# EmbiggenedKeyboard.net
KiCad netlist of a schematic drawn in EAGLE
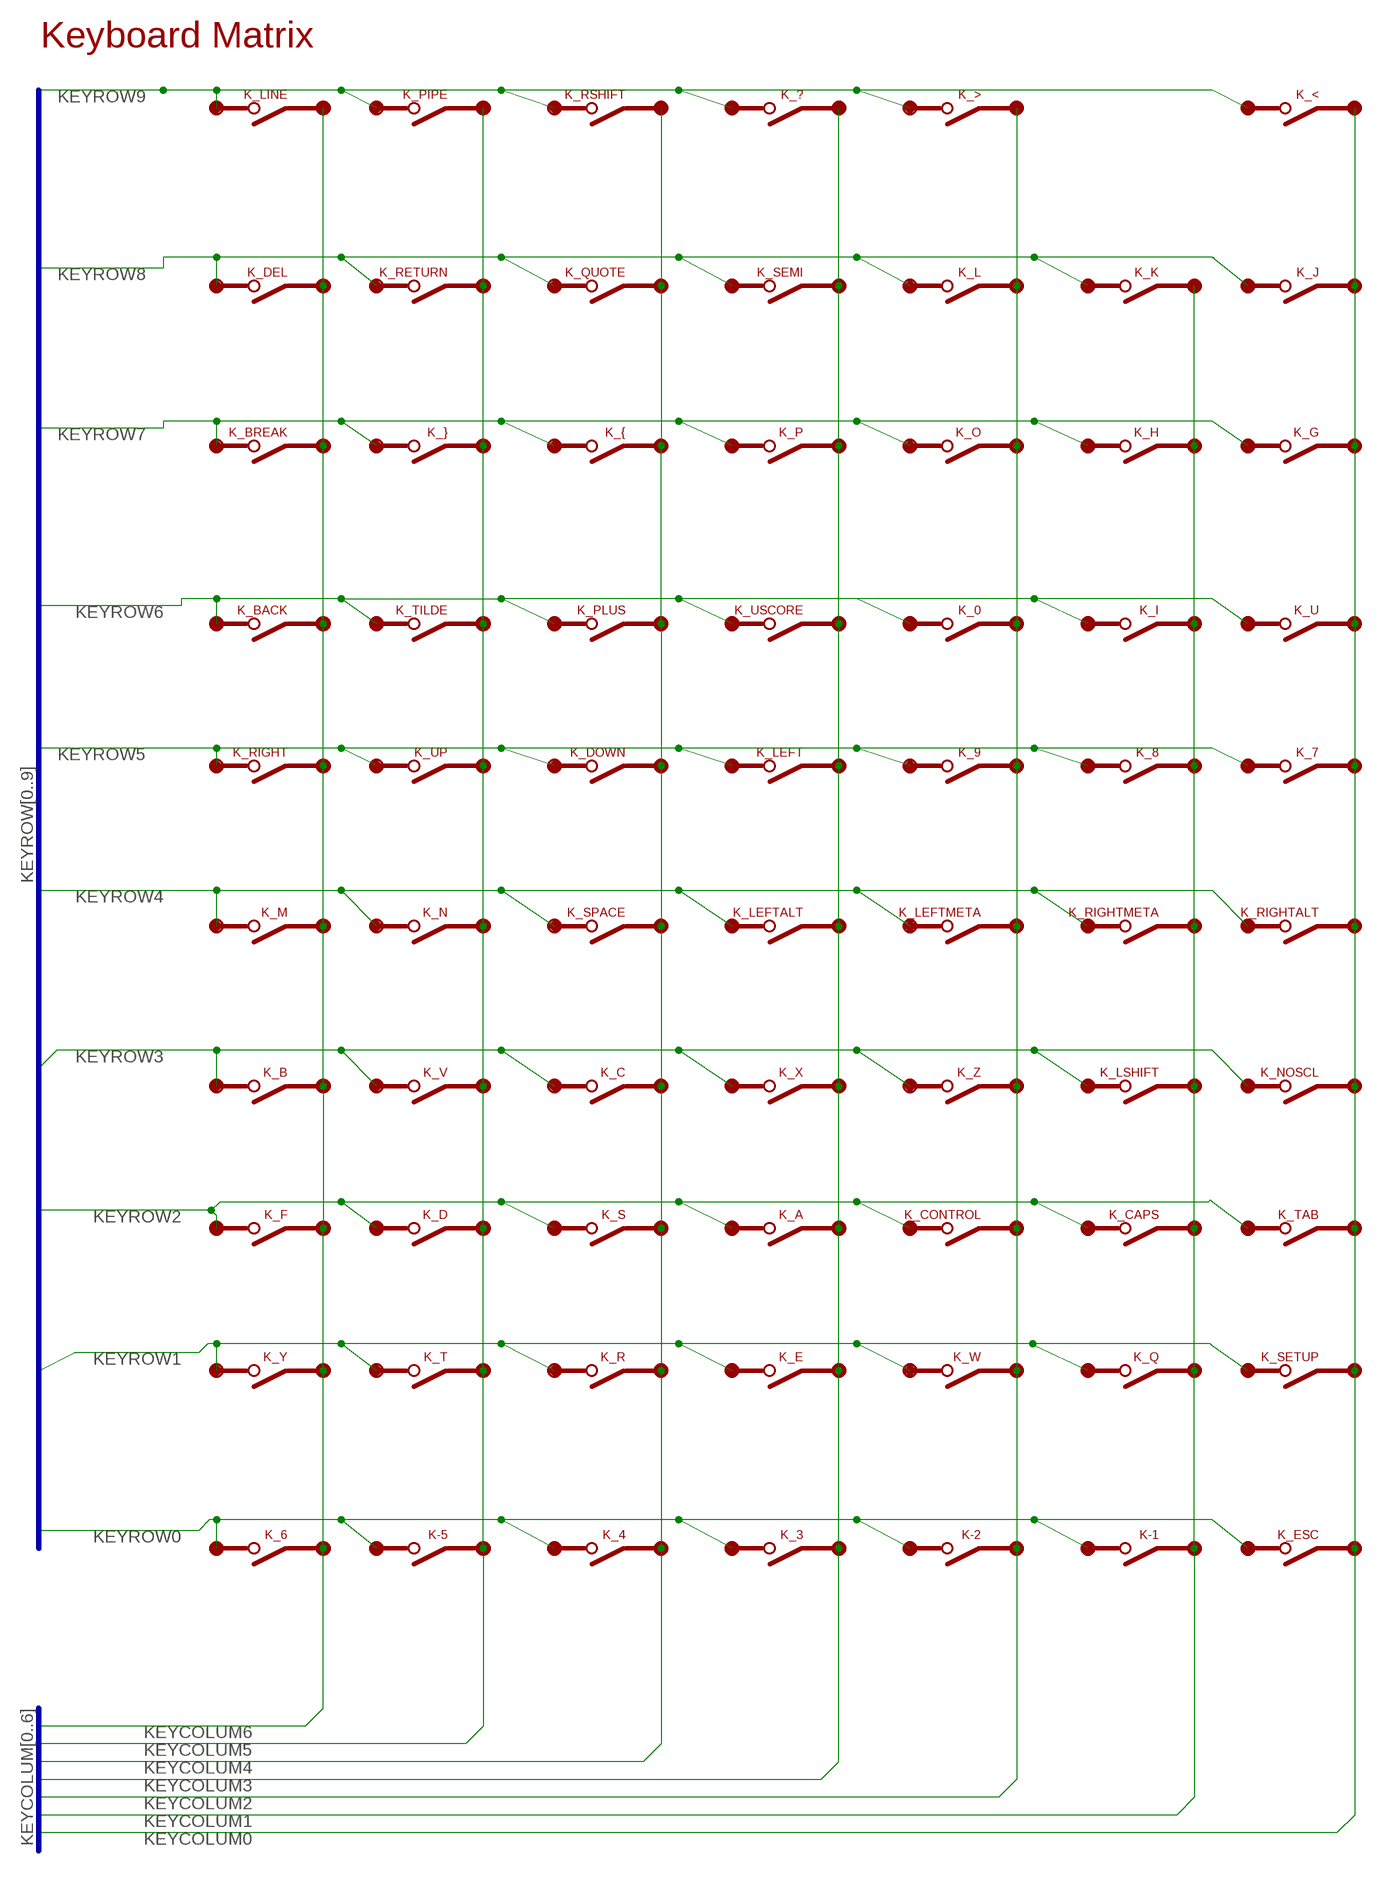
[diagram p0: schematic, sheet 1, part 1 of 2]
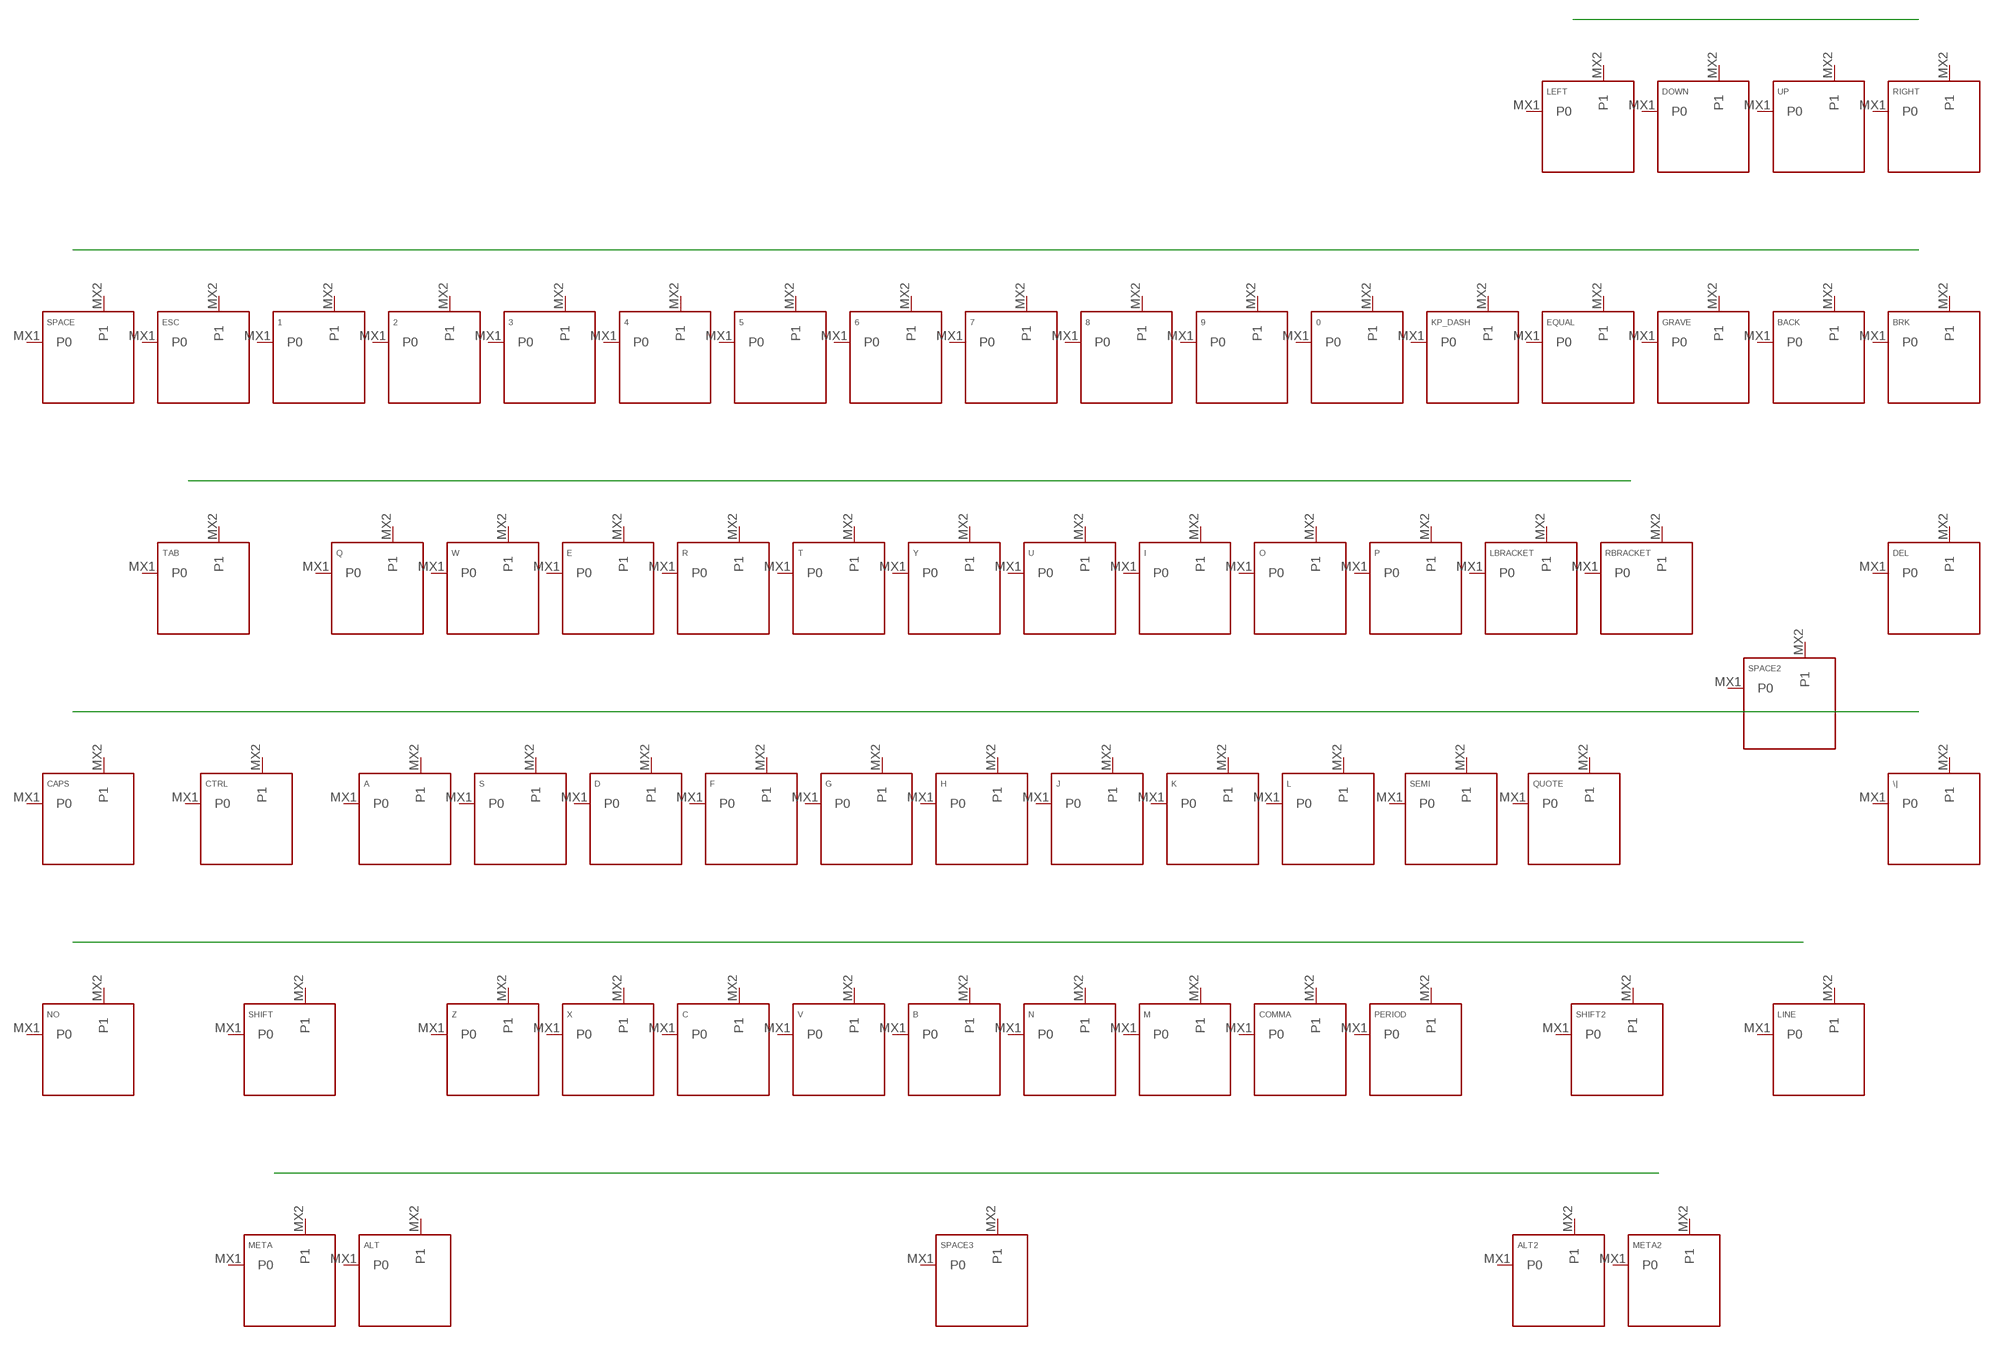
[diagram p1: schematic, sheet 1, part 2 of 2]

(export (version "E")
  (design (tool "Eeschema 10.0.6"))
  (components
    (comp (ref "0")
      (value "KEYSWITCH-PLAIN-MX-1U")
      (footprint "eagle-import:MX-1U")
      (libsource (lib "eagle-import") (part "KEYSWITCH-PLAIN-MX-1U"))
    )
    (comp (ref "1")
      (value "KEYSWITCH-PLAIN-MX-1U")
      (footprint "eagle-import:MX-1U")
      (libsource (lib "eagle-import") (part "KEYSWITCH-PLAIN-MX-1U"))
    )
    (comp (ref "2")
      (value "KEYSWITCH-PLAIN-MX-1U")
      (footprint "eagle-import:MX-1U")
      (libsource (lib "eagle-import") (part "KEYSWITCH-PLAIN-MX-1U"))
    )
    (comp (ref "3")
      (value "KEYSWITCH-PLAIN-MX-1U")
      (footprint "eagle-import:MX-1U")
      (libsource (lib "eagle-import") (part "KEYSWITCH-PLAIN-MX-1U"))
    )
    (comp (ref "4")
      (value "KEYSWITCH-PLAIN-MX-1U")
      (footprint "eagle-import:MX-1U")
      (libsource (lib "eagle-import") (part "KEYSWITCH-PLAIN-MX-1U"))
    )
    (comp (ref "5")
      (value "KEYSWITCH-PLAIN-MX-1U")
      (footprint "eagle-import:MX-1U")
      (libsource (lib "eagle-import") (part "KEYSWITCH-PLAIN-MX-1U"))
    )
    (comp (ref "6")
      (value "KEYSWITCH-PLAIN-MX-1U")
      (footprint "eagle-import:MX-1U")
      (libsource (lib "eagle-import") (part "KEYSWITCH-PLAIN-MX-1U"))
    )
    (comp (ref "7")
      (value "KEYSWITCH-PLAIN-MX-1U")
      (footprint "eagle-import:MX-1U")
      (libsource (lib "eagle-import") (part "KEYSWITCH-PLAIN-MX-1U"))
    )
    (comp (ref "8")
      (value "KEYSWITCH-PLAIN-MX-1U")
      (footprint "eagle-import:MX-1U")
      (libsource (lib "eagle-import") (part "KEYSWITCH-PLAIN-MX-1U"))
    )
    (comp (ref "9")
      (value "KEYSWITCH-PLAIN-MX-1U")
      (footprint "eagle-import:MX-1U")
      (libsource (lib "eagle-import") (part "KEYSWITCH-PLAIN-MX-1U"))
    )
    (comp (ref "A")
      (value "KEYSWITCH-PLAIN-MX-1U")
      (footprint "eagle-import:MX-1U")
      (libsource (lib "eagle-import") (part "KEYSWITCH-PLAIN-MX-1U"))
    )
    (comp (ref "ALT")
      (value "KEYSWITCH-PLAIN-MX-1U")
      (footprint "eagle-import:MX-1U")
      (libsource (lib "eagle-import") (part "KEYSWITCH-PLAIN-MX-1U"))
    )
    (comp (ref "ALT2")
      (value "KEYSWITCH-PLAIN-MX-1U")
      (footprint "eagle-import:MX-1U")
      (libsource (lib "eagle-import") (part "KEYSWITCH-PLAIN-MX-1U"))
    )
    (comp (ref "B")
      (value "KEYSWITCH-PLAIN-MX-1U")
      (footprint "eagle-import:MX-1U")
      (libsource (lib "eagle-import") (part "KEYSWITCH-PLAIN-MX-1U"))
    )
    (comp (ref "BACK")
      (value "KEYSWITCH-PLAIN-MX-1U")
      (footprint "eagle-import:MX-1U")
      (libsource (lib "eagle-import") (part "KEYSWITCH-PLAIN-MX-1U"))
    )
    (comp (ref "BRK")
      (value "KEYSWITCH-PLAIN-MX-1U")
      (footprint "eagle-import:MX-1U")
      (libsource (lib "eagle-import") (part "KEYSWITCH-PLAIN-MX-1U"))
    )
    (comp (ref "C")
      (value "KEYSWITCH-PLAIN-MX-1U")
      (footprint "eagle-import:MX-1U")
      (libsource (lib "eagle-import") (part "KEYSWITCH-PLAIN-MX-1U"))
    )
    (comp (ref "CAPS")
      (value "KEYSWITCH-PLAIN-MX-1U")
      (footprint "eagle-import:MX-1U")
      (libsource (lib "eagle-import") (part "KEYSWITCH-PLAIN-MX-1U"))
    )
    (comp (ref "COMMA")
      (value "KEYSWITCH-PLAIN-MX-1U")
      (footprint "eagle-import:MX-1U")
      (libsource (lib "eagle-import") (part "KEYSWITCH-PLAIN-MX-1U"))
    )
    (comp (ref "CTRL")
      (value "KEYSWITCH-PLAIN-MX-1U")
      (footprint "eagle-import:MX-1U")
      (libsource (lib "eagle-import") (part "KEYSWITCH-PLAIN-MX-1U"))
    )
    (comp (ref "D")
      (value "KEYSWITCH-PLAIN-MX-1U")
      (footprint "eagle-import:MX-1U")
      (libsource (lib "eagle-import") (part "KEYSWITCH-PLAIN-MX-1U"))
    )
    (comp (ref "DEL")
      (value "KEYSWITCH-PLAIN-MX-1U")
      (footprint "eagle-import:MX-1U")
      (libsource (lib "eagle-import") (part "KEYSWITCH-PLAIN-MX-1U"))
    )
    (comp (ref "DOWN")
      (value "KEYSWITCH-PLAIN-MX-1U")
      (footprint "eagle-import:MX-1U")
      (libsource (lib "eagle-import") (part "KEYSWITCH-PLAIN-MX-1U"))
    )
    (comp (ref "E")
      (value "KEYSWITCH-PLAIN-MX-1U")
      (footprint "eagle-import:MX-1U")
      (libsource (lib "eagle-import") (part "KEYSWITCH-PLAIN-MX-1U"))
    )
    (comp (ref "EQUAL")
      (value "KEYSWITCH-PLAIN-MX-1U")
      (footprint "eagle-import:MX-1U")
      (libsource (lib "eagle-import") (part "KEYSWITCH-PLAIN-MX-1U"))
    )
    (comp (ref "ESC")
      (value "KEYSWITCH-PLAIN-MX-1U")
      (footprint "eagle-import:MX-1U")
      (libsource (lib "eagle-import") (part "KEYSWITCH-PLAIN-MX-1U"))
    )
    (comp (ref "F")
      (value "KEYSWITCH-PLAIN-MX-1U")
      (footprint "eagle-import:MX-1U")
      (libsource (lib "eagle-import") (part "KEYSWITCH-PLAIN-MX-1U"))
    )
    (comp (ref "G")
      (value "KEYSWITCH-PLAIN-MX-1U")
      (footprint "eagle-import:MX-1U")
      (libsource (lib "eagle-import") (part "KEYSWITCH-PLAIN-MX-1U"))
    )
    (comp (ref "GRAVE")
      (value "KEYSWITCH-PLAIN-MX-1U")
      (footprint "eagle-import:MX-1U")
      (libsource (lib "eagle-import") (part "KEYSWITCH-PLAIN-MX-1U"))
    )
    (comp (ref "H")
      (value "KEYSWITCH-PLAIN-MX-1U")
      (footprint "eagle-import:MX-1U")
      (libsource (lib "eagle-import") (part "KEYSWITCH-PLAIN-MX-1U"))
    )
    (comp (ref "I")
      (value "KEYSWITCH-PLAIN-MX-1U")
      (footprint "eagle-import:MX-1U")
      (libsource (lib "eagle-import") (part "KEYSWITCH-PLAIN-MX-1U"))
    )
    (comp (ref "J")
      (value "KEYSWITCH-PLAIN-MX-1U")
      (footprint "eagle-import:MX-1U")
      (libsource (lib "eagle-import") (part "KEYSWITCH-PLAIN-MX-1U"))
    )
    (comp (ref "K")
      (value "KEYSWITCH-PLAIN-MX-1U")
      (footprint "eagle-import:MX-1U")
      (libsource (lib "eagle-import") (part "KEYSWITCH-PLAIN-MX-1U"))
    )
    (comp (ref "K-1")
      (value "1U_PAD")
      (footprint "eagle-import:SILICONE_SWITCH")
      (libsource (lib "eagle-import") (part "1U_PAD"))
    )
    (comp (ref "K-2")
      (value "1U_PAD")
      (footprint "eagle-import:SILICONE_SWITCH")
      (libsource (lib "eagle-import") (part "1U_PAD"))
    )
    (comp (ref "K-5")
      (value "1U_PAD")
      (footprint "eagle-import:SILICONE_SWITCH")
      (libsource (lib "eagle-import") (part "1U_PAD"))
    )
    (comp (ref "KP_DASH")
      (value "KEYSWITCH-PLAIN-MX-1U")
      (footprint "eagle-import:MX-1U")
      (libsource (lib "eagle-import") (part "KEYSWITCH-PLAIN-MX-1U"))
    )
    (comp (ref "K_0")
      (value "1U_PAD")
      (footprint "eagle-import:SILICONE_SWITCH")
      (libsource (lib "eagle-import") (part "1U_PAD"))
    )
    (comp (ref "K_3")
      (value "1U_PAD")
      (footprint "eagle-import:SILICONE_SWITCH")
      (libsource (lib "eagle-import") (part "1U_PAD"))
    )
    (comp (ref "K_4")
      (value "1U_PAD")
      (footprint "eagle-import:SILICONE_SWITCH")
      (libsource (lib "eagle-import") (part "1U_PAD"))
    )
    (comp (ref "K_6")
      (value "1U_PAD")
      (footprint "eagle-import:SILICONE_SWITCH")
      (libsource (lib "eagle-import") (part "1U_PAD"))
    )
    (comp (ref "K_7")
      (value "1U_PAD")
      (footprint "eagle-import:SILICONE_SWITCH")
      (libsource (lib "eagle-import") (part "1U_PAD"))
    )
    (comp (ref "K_8")
      (value "1U_PAD")
      (footprint "eagle-import:SILICONE_SWITCH")
      (libsource (lib "eagle-import") (part "1U_PAD"))
    )
    (comp (ref "K_9")
      (value "1U_PAD")
      (footprint "eagle-import:SILICONE_SWITCH")
      (libsource (lib "eagle-import") (part "1U_PAD"))
    )
    (comp (ref "K_<")
      (value "1U_PAD")
      (footprint "eagle-import:SILICONE_SWITCH")
      (libsource (lib "eagle-import") (part "1U_PAD"))
    )
    (comp (ref "K_>")
      (value "1U_PAD")
      (footprint "eagle-import:SILICONE_SWITCH")
      (libsource (lib "eagle-import") (part "1U_PAD"))
    )
    (comp (ref "K_?")
      (value "1U_PAD")
      (footprint "eagle-import:SILICONE_SWITCH")
      (libsource (lib "eagle-import") (part "1U_PAD"))
    )
    (comp (ref "K_A")
      (value "1U_PAD")
      (footprint "eagle-import:SILICONE_SWITCH")
      (libsource (lib "eagle-import") (part "1U_PAD"))
    )
    (comp (ref "K_B")
      (value "1U_PAD")
      (footprint "eagle-import:SILICONE_SWITCH")
      (libsource (lib "eagle-import") (part "1U_PAD"))
    )
    (comp (ref "K_BACK")
      (value "1U_PAD")
      (footprint "eagle-import:SILICONE_SWITCH")
      (libsource (lib "eagle-import") (part "1U_PAD"))
    )
    (comp (ref "K_BREAK")
      (value "1U_PAD")
      (footprint "eagle-import:SILICONE_SWITCH")
      (libsource (lib "eagle-import") (part "1U_PAD"))
    )
    (comp (ref "K_C")
      (value "1U_PAD")
      (footprint "eagle-import:SILICONE_SWITCH")
      (libsource (lib "eagle-import") (part "1U_PAD"))
    )
    (comp (ref "K_CAPS")
      (value "1U_PAD")
      (footprint "eagle-import:SILICONE_SWITCH")
      (libsource (lib "eagle-import") (part "1U_PAD"))
    )
    (comp (ref "K_CONTROL")
      (value "2U_PAD")
      (footprint "eagle-import:SILICONE_SWITCH_2U")
      (libsource (lib "eagle-import") (part "2U_PAD"))
    )
    (comp (ref "K_D")
      (value "1U_PAD")
      (footprint "eagle-import:SILICONE_SWITCH")
      (libsource (lib "eagle-import") (part "1U_PAD"))
    )
    (comp (ref "K_DEL")
      (value "1U_PAD")
      (footprint "eagle-import:SILICONE_SWITCH")
      (libsource (lib "eagle-import") (part "1U_PAD"))
    )
    (comp (ref "K_DOWN")
      (value "1U_PAD")
      (footprint "eagle-import:SILICONE_SWITCH")
      (libsource (lib "eagle-import") (part "1U_PAD"))
    )
    (comp (ref "K_E")
      (value "1U_PAD")
      (footprint "eagle-import:SILICONE_SWITCH")
      (libsource (lib "eagle-import") (part "1U_PAD"))
    )
    (comp (ref "K_ESC")
      (value "1U_PAD")
      (footprint "eagle-import:SILICONE_SWITCH")
      (libsource (lib "eagle-import") (part "1U_PAD"))
    )
    (comp (ref "K_F")
      (value "1U_PAD")
      (footprint "eagle-import:SILICONE_SWITCH")
      (libsource (lib "eagle-import") (part "1U_PAD"))
    )
    (comp (ref "K_G")
      (value "1U_PAD")
      (footprint "eagle-import:SILICONE_SWITCH")
      (libsource (lib "eagle-import") (part "1U_PAD"))
    )
    (comp (ref "K_H")
      (value "1U_PAD")
      (footprint "eagle-import:SILICONE_SWITCH")
      (libsource (lib "eagle-import") (part "1U_PAD"))
    )
    (comp (ref "K_I")
      (value "1U_PAD")
      (footprint "eagle-import:SILICONE_SWITCH")
      (libsource (lib "eagle-import") (part "1U_PAD"))
    )
    (comp (ref "K_J")
      (value "1U_PAD")
      (footprint "eagle-import:SILICONE_SWITCH")
      (libsource (lib "eagle-import") (part "1U_PAD"))
    )
    (comp (ref "K_K")
      (value "1U_PAD")
      (footprint "eagle-import:SILICONE_SWITCH")
      (libsource (lib "eagle-import") (part "1U_PAD"))
    )
    (comp (ref "K_L")
      (value "1U_PAD")
      (footprint "eagle-import:SILICONE_SWITCH")
      (libsource (lib "eagle-import") (part "1U_PAD"))
    )
    (comp (ref "K_LEFT")
      (value "1U_PAD")
      (footprint "eagle-import:SILICONE_SWITCH")
      (libsource (lib "eagle-import") (part "1U_PAD"))
    )
    (comp (ref "K_LEFTALT")
      (value "1U_PAD")
      (footprint "eagle-import:SILICONE_SWITCH")
      (libsource (lib "eagle-import") (part "1U_PAD"))
    )
    (comp (ref "K_LEFTMETA")
      (value "1U_PAD")
      (footprint "eagle-import:SILICONE_SWITCH")
      (libsource (lib "eagle-import") (part "1U_PAD"))
    )
    (comp (ref "K_LINE")
      (value "1U_PAD")
      (footprint "eagle-import:SILICONE_SWITCH")
      (libsource (lib "eagle-import") (part "1U_PAD"))
    )
    (comp (ref "K_LSHIFT")
      (value "2U_PAD")
      (footprint "eagle-import:SILICONE_SWITCH_2U")
      (libsource (lib "eagle-import") (part "2U_PAD"))
    )
    (comp (ref "K_M")
      (value "1U_PAD")
      (footprint "eagle-import:SILICONE_SWITCH")
      (libsource (lib "eagle-import") (part "1U_PAD"))
    )
    (comp (ref "K_N")
      (value "1U_PAD")
      (footprint "eagle-import:SILICONE_SWITCH")
      (libsource (lib "eagle-import") (part "1U_PAD"))
    )
    (comp (ref "K_NOSCL")
      (value "1U_PAD")
      (footprint "eagle-import:SILICONE_SWITCH")
      (libsource (lib "eagle-import") (part "1U_PAD"))
    )
    (comp (ref "K_O")
      (value "1U_PAD")
      (footprint "eagle-import:SILICONE_SWITCH")
      (libsource (lib "eagle-import") (part "1U_PAD"))
    )
    (comp (ref "K_P")
      (value "1U_PAD")
      (footprint "eagle-import:SILICONE_SWITCH")
      (libsource (lib "eagle-import") (part "1U_PAD"))
    )
    (comp (ref "K_PIPE")
      (value "1U_PAD")
      (footprint "eagle-import:SILICONE_SWITCH")
      (libsource (lib "eagle-import") (part "1U_PAD"))
    )
    (comp (ref "K_PLUS")
      (value "1U_PAD")
      (footprint "eagle-import:SILICONE_SWITCH")
      (libsource (lib "eagle-import") (part "1U_PAD"))
    )
    (comp (ref "K_Q")
      (value "1U_PAD")
      (footprint "eagle-import:SILICONE_SWITCH")
      (libsource (lib "eagle-import") (part "1U_PAD"))
    )
    (comp (ref "K_QUOTE")
      (value "1U_PAD")
      (footprint "eagle-import:SILICONE_SWITCH")
      (libsource (lib "eagle-import") (part "1U_PAD"))
    )
    (comp (ref "K_R")
      (value "1U_PAD")
      (footprint "eagle-import:SILICONE_SWITCH")
      (libsource (lib "eagle-import") (part "1U_PAD"))
    )
    (comp (ref "K_RETURN")
      (value "RETURN_PAD")
      (footprint "eagle-import:SILICONE_RETURN")
      (libsource (lib "eagle-import") (part "RETURN_PAD"))
    )
    (comp (ref "K_RIGHT")
      (value "1U_PAD")
      (footprint "eagle-import:SILICONE_SWITCH")
      (libsource (lib "eagle-import") (part "1U_PAD"))
    )
    (comp (ref "K_RIGHTALT")
      (value "1U_PAD")
      (footprint "eagle-import:SILICONE_SWITCH")
      (libsource (lib "eagle-import") (part "1U_PAD"))
    )
    (comp (ref "K_RIGHTMETA")
      (value "1U_PAD")
      (footprint "eagle-import:SILICONE_SWITCH")
      (libsource (lib "eagle-import") (part "1U_PAD"))
    )
    (comp (ref "K_RSHIFT")
      (value "2U_PAD")
      (footprint "eagle-import:SILICONE_SWITCH_2U")
      (libsource (lib "eagle-import") (part "2U_PAD"))
    )
    (comp (ref "K_S")
      (value "1U_PAD")
      (footprint "eagle-import:SILICONE_SWITCH")
      (libsource (lib "eagle-import") (part "1U_PAD"))
    )
    (comp (ref "K_SEMI")
      (value "1U_PAD")
      (footprint "eagle-import:SILICONE_SWITCH")
      (libsource (lib "eagle-import") (part "1U_PAD"))
    )
    (comp (ref "K_SETUP")
      (value "2U_PAD")
      (footprint "eagle-import:SILICONE_SWITCH_2U")
      (libsource (lib "eagle-import") (part "2U_PAD"))
    )
    (comp (ref "K_SPACE")
      (value "SPACE_PAD")
      (footprint "eagle-import:SILICONE_SPACE")
      (libsource (lib "eagle-import") (part "SPACE_PAD"))
    )
    (comp (ref "K_T")
      (value "1U_PAD")
      (footprint "eagle-import:SILICONE_SWITCH")
      (libsource (lib "eagle-import") (part "1U_PAD"))
    )
    (comp (ref "K_TAB")
      (value "1U_PAD")
      (footprint "eagle-import:SILICONE_SWITCH")
      (libsource (lib "eagle-import") (part "1U_PAD"))
    )
    (comp (ref "K_TILDE")
      (value "1U_PAD")
      (footprint "eagle-import:SILICONE_SWITCH")
      (libsource (lib "eagle-import") (part "1U_PAD"))
    )
    (comp (ref "K_U")
      (value "1U_PAD")
      (footprint "eagle-import:SILICONE_SWITCH")
      (libsource (lib "eagle-import") (part "1U_PAD"))
    )
    (comp (ref "K_UP")
      (value "1U_PAD")
      (footprint "eagle-import:SILICONE_SWITCH")
      (libsource (lib "eagle-import") (part "1U_PAD"))
    )
    (comp (ref "K_USCORE")
      (value "1U_PAD")
      (footprint "eagle-import:SILICONE_SWITCH")
      (libsource (lib "eagle-import") (part "1U_PAD"))
    )
    (comp (ref "K_V")
      (value "1U_PAD")
      (footprint "eagle-import:SILICONE_SWITCH")
      (libsource (lib "eagle-import") (part "1U_PAD"))
    )
    (comp (ref "K_W")
      (value "1U_PAD")
      (footprint "eagle-import:SILICONE_SWITCH")
      (libsource (lib "eagle-import") (part "1U_PAD"))
    )
    (comp (ref "K_X")
      (value "1U_PAD")
      (footprint "eagle-import:SILICONE_SWITCH")
      (libsource (lib "eagle-import") (part "1U_PAD"))
    )
    (comp (ref "K_Y")
      (value "1U_PAD")
      (footprint "eagle-import:SILICONE_SWITCH")
      (libsource (lib "eagle-import") (part "1U_PAD"))
    )
    (comp (ref "K_Z")
      (value "1U_PAD")
      (footprint "eagle-import:SILICONE_SWITCH")
      (libsource (lib "eagle-import") (part "1U_PAD"))
    )
    (comp (ref "K_{")
      (value "1U_PAD")
      (footprint "eagle-import:SILICONE_SWITCH")
      (libsource (lib "eagle-import") (part "1U_PAD"))
    )
    (comp (ref "K_}")
      (value "1U_PAD")
      (footprint "eagle-import:SILICONE_SWITCH")
      (libsource (lib "eagle-import") (part "1U_PAD"))
    )
    (comp (ref "L")
      (value "KEYSWITCH-PLAIN-MX-1U")
      (footprint "eagle-import:MX-1U")
      (libsource (lib "eagle-import") (part "KEYSWITCH-PLAIN-MX-1U"))
    )
    (comp (ref "LBRACKET")
      (value "KEYSWITCH-PLAIN-MX-1U")
      (footprint "eagle-import:MX-1U")
      (libsource (lib "eagle-import") (part "KEYSWITCH-PLAIN-MX-1U"))
    )
    (comp (ref "LEFT")
      (value "KEYSWITCH-PLAIN-MX-1U")
      (footprint "eagle-import:MX-1U")
      (libsource (lib "eagle-import") (part "KEYSWITCH-PLAIN-MX-1U"))
    )
    (comp (ref "LINE")
      (value "KEYSWITCH-PLAIN-MX-1U")
      (footprint "eagle-import:MX-1U")
      (libsource (lib "eagle-import") (part "KEYSWITCH-PLAIN-MX-1U"))
    )
    (comp (ref "M")
      (value "KEYSWITCH-PLAIN-MX-1U")
      (footprint "eagle-import:MX-1U")
      (libsource (lib "eagle-import") (part "KEYSWITCH-PLAIN-MX-1U"))
    )
    (comp (ref "META")
      (value "KEYSWITCH-PLAIN-MX-1U")
      (footprint "eagle-import:MX-1U")
      (libsource (lib "eagle-import") (part "KEYSWITCH-PLAIN-MX-1U"))
    )
    (comp (ref "META2")
      (value "KEYSWITCH-PLAIN-MX-1U")
      (footprint "eagle-import:MX-1U")
      (libsource (lib "eagle-import") (part "KEYSWITCH-PLAIN-MX-1U"))
    )
    (comp (ref "N")
      (value "KEYSWITCH-PLAIN-MX-1U")
      (footprint "eagle-import:MX-1U")
      (libsource (lib "eagle-import") (part "KEYSWITCH-PLAIN-MX-1U"))
    )
    (comp (ref "NO")
      (value "KEYSWITCH-PLAIN-MX-1U")
      (footprint "eagle-import:MX-1U")
      (libsource (lib "eagle-import") (part "KEYSWITCH-PLAIN-MX-1U"))
    )
    (comp (ref "O")
      (value "KEYSWITCH-PLAIN-MX-1U")
      (footprint "eagle-import:MX-1U")
      (libsource (lib "eagle-import") (part "KEYSWITCH-PLAIN-MX-1U"))
    )
    (comp (ref "P")
      (value "KEYSWITCH-PLAIN-MX-1U")
      (footprint "eagle-import:MX-1U")
      (libsource (lib "eagle-import") (part "KEYSWITCH-PLAIN-MX-1U"))
    )
    (comp (ref "PERIOD")
      (value "KEYSWITCH-PLAIN-MX-1U")
      (footprint "eagle-import:MX-1U")
      (libsource (lib "eagle-import") (part "KEYSWITCH-PLAIN-MX-1U"))
    )
    (comp (ref "Q")
      (value "KEYSWITCH-PLAIN-MX-1U")
      (footprint "eagle-import:MX-1U")
      (libsource (lib "eagle-import") (part "KEYSWITCH-PLAIN-MX-1U"))
    )
    (comp (ref "QUOTE")
      (value "KEYSWITCH-PLAIN-MX-1U")
      (footprint "eagle-import:MX-1U")
      (libsource (lib "eagle-import") (part "KEYSWITCH-PLAIN-MX-1U"))
    )
    (comp (ref "R")
      (value "KEYSWITCH-PLAIN-MX-1U")
      (footprint "eagle-import:MX-1U")
      (libsource (lib "eagle-import") (part "KEYSWITCH-PLAIN-MX-1U"))
    )
    (comp (ref "RBRACKET")
      (value "KEYSWITCH-PLAIN-MX-1U")
      (footprint "eagle-import:MX-1U")
      (libsource (lib "eagle-import") (part "KEYSWITCH-PLAIN-MX-1U"))
    )
    (comp (ref "RIGHT")
      (value "KEYSWITCH-PLAIN-MX-1U")
      (footprint "eagle-import:MX-1U")
      (libsource (lib "eagle-import") (part "KEYSWITCH-PLAIN-MX-1U"))
    )
    (comp (ref "S")
      (value "KEYSWITCH-PLAIN-MX-1U")
      (footprint "eagle-import:MX-1U")
      (libsource (lib "eagle-import") (part "KEYSWITCH-PLAIN-MX-1U"))
    )
    (comp (ref "SEMI")
      (value "KEYSWITCH-PLAIN-MX-1U")
      (footprint "eagle-import:MX-1U")
      (libsource (lib "eagle-import") (part "KEYSWITCH-PLAIN-MX-1U"))
    )
    (comp (ref "SHIFT")
      (value "KEYSWITCH-PLAIN-MX-1U")
      (footprint "eagle-import:MX-1U")
      (libsource (lib "eagle-import") (part "KEYSWITCH-PLAIN-MX-1U"))
    )
    (comp (ref "SHIFT2")
      (value "KEYSWITCH-PLAIN-MX-1U")
      (footprint "eagle-import:MX-1U")
      (libsource (lib "eagle-import") (part "KEYSWITCH-PLAIN-MX-1U"))
    )
    (comp (ref "SPACE")
      (value "KEYSWITCH-PLAIN-MX-1U")
      (footprint "eagle-import:MX-1U")
      (libsource (lib "eagle-import") (part "KEYSWITCH-PLAIN-MX-1U"))
    )
    (comp (ref "SPACE2")
      (value "KEYSWITCH-PLAIN-MX-1U")
      (footprint "eagle-import:MX-1U")
      (libsource (lib "eagle-import") (part "KEYSWITCH-PLAIN-MX-1U"))
    )
    (comp (ref "SPACE3")
      (value "KEYSWITCH-PLAIN-MX-1U")
      (footprint "eagle-import:MX-1U")
      (libsource (lib "eagle-import") (part "KEYSWITCH-PLAIN-MX-1U"))
    )
    (comp (ref "T")
      (value "KEYSWITCH-PLAIN-MX-1U")
      (footprint "eagle-import:MX-1U")
      (libsource (lib "eagle-import") (part "KEYSWITCH-PLAIN-MX-1U"))
    )
    (comp (ref "TAB")
      (value "KEYSWITCH-PLAIN-MX-1U")
      (footprint "eagle-import:MX-1U")
      (libsource (lib "eagle-import") (part "KEYSWITCH-PLAIN-MX-1U"))
    )
    (comp (ref "U")
      (value "KEYSWITCH-PLAIN-MX-1U")
      (footprint "eagle-import:MX-1U")
      (libsource (lib "eagle-import") (part "KEYSWITCH-PLAIN-MX-1U"))
    )
    (comp (ref "UP")
      (value "KEYSWITCH-PLAIN-MX-1U")
      (footprint "eagle-import:MX-1U")
      (libsource (lib "eagle-import") (part "KEYSWITCH-PLAIN-MX-1U"))
    )
    (comp (ref "V")
      (value "KEYSWITCH-PLAIN-MX-1U")
      (footprint "eagle-import:MX-1U")
      (libsource (lib "eagle-import") (part "KEYSWITCH-PLAIN-MX-1U"))
    )
    (comp (ref "W")
      (value "KEYSWITCH-PLAIN-MX-1U")
      (footprint "eagle-import:MX-1U")
      (libsource (lib "eagle-import") (part "KEYSWITCH-PLAIN-MX-1U"))
    )
    (comp (ref "X")
      (value "KEYSWITCH-PLAIN-MX-1U")
      (footprint "eagle-import:MX-1U")
      (libsource (lib "eagle-import") (part "KEYSWITCH-PLAIN-MX-1U"))
    )
    (comp (ref "Y")
      (value "KEYSWITCH-PLAIN-MX-1U")
      (footprint "eagle-import:MX-1U")
      (libsource (lib "eagle-import") (part "KEYSWITCH-PLAIN-MX-1U"))
    )
    (comp (ref "Z")
      (value "KEYSWITCH-PLAIN-MX-1U")
      (footprint "eagle-import:MX-1U")
      (libsource (lib "eagle-import") (part "KEYSWITCH-PLAIN-MX-1U"))
    )
    (comp (ref "\\|")
      (value "KEYSWITCH-PLAIN-MX-1U")
      (footprint "eagle-import:MX-1U")
      (libsource (lib "eagle-import") (part "KEYSWITCH-PLAIN-MX-1U"))
    )
  )
  (nets
    (net (code "1") (name "/KEYCOLUM0") (class "Default")
      (node (ref "K_7") (pin "P$2") (pinfunction "P$2_P$2") (pintype "bidirectional"))
      (node (ref "K_<") (pin "P$2") (pinfunction "P$2_P$2") (pintype "bidirectional"))
      (node (ref "K_ESC") (pin "P$2") (pinfunction "P$2_P$2") (pintype "bidirectional"))
      (node (ref "K_G") (pin "P$2") (pinfunction "P$2_P$2") (pintype "bidirectional"))
      (node (ref "K_J") (pin "P$2") (pinfunction "P$2_P$2") (pintype "bidirectional"))
      (node (ref "K_NOSCL") (pin "P$2") (pinfunction "P$2_P$2") (pintype "bidirectional"))
      (node (ref "K_RIGHTALT") (pin "P$2") (pinfunction "P$2_P$2") (pintype "bidirectional"))
      (node (ref "K_SETUP") (pin "P$2") (pinfunction "P$2_P$2") (pintype "bidirectional"))
      (node (ref "K_TAB") (pin "P$2") (pinfunction "P$2_P$2") (pintype "bidirectional"))
      (node (ref "K_U") (pin "P$2") (pinfunction "P$2_P$2") (pintype "bidirectional"))
    )
    (net (code "2") (name "/KEYCOLUM1") (class "Default")
      (node (ref "K-1") (pin "P$2") (pinfunction "P$2_P$2") (pintype "bidirectional"))
      (node (ref "K_8") (pin "P$2") (pinfunction "P$2_P$2") (pintype "bidirectional"))
      (node (ref "K_CAPS") (pin "P$2") (pinfunction "P$2_P$2") (pintype "bidirectional"))
      (node (ref "K_H") (pin "P$2") (pinfunction "P$2_P$2") (pintype "bidirectional"))
      (node (ref "K_I") (pin "P$2") (pinfunction "P$2_P$2") (pintype "bidirectional"))
      (node (ref "K_K") (pin "P$2") (pinfunction "P$2_P$2") (pintype "bidirectional"))
      (node (ref "K_LSHIFT") (pin "P$2") (pinfunction "P$2_P$2") (pintype "bidirectional"))
      (node (ref "K_Q") (pin "P$2") (pinfunction "P$2_P$2") (pintype "bidirectional"))
      (node (ref "K_RIGHTMETA") (pin "P$2") (pinfunction "P$2_P$2") (pintype "bidirectional"))
    )
    (net (code "3") (name "/KEYCOLUM2") (class "Default")
      (node (ref "K-2") (pin "P$2") (pinfunction "P$2_P$2") (pintype "bidirectional"))
      (node (ref "K_0") (pin "P$2") (pinfunction "P$2_P$2") (pintype "bidirectional"))
      (node (ref "K_9") (pin "P$2") (pinfunction "P$2_P$2") (pintype "bidirectional"))
      (node (ref "K_>") (pin "P$2") (pinfunction "P$2_P$2") (pintype "bidirectional"))
      (node (ref "K_CONTROL") (pin "P$2") (pinfunction "P$2_P$2") (pintype "bidirectional"))
      (node (ref "K_L") (pin "P$2") (pinfunction "P$2_P$2") (pintype "bidirectional"))
      (node (ref "K_LEFTMETA") (pin "P$2") (pinfunction "P$2_P$2") (pintype "bidirectional"))
      (node (ref "K_O") (pin "P$2") (pinfunction "P$2_P$2") (pintype "bidirectional"))
      (node (ref "K_W") (pin "P$2") (pinfunction "P$2_P$2") (pintype "bidirectional"))
      (node (ref "K_Z") (pin "P$2") (pinfunction "P$2_P$2") (pintype "bidirectional"))
    )
    (net (code "4") (name "/KEYCOLUM3") (class "Default")
      (node (ref "K_3") (pin "P$2") (pinfunction "P$2_P$2") (pintype "bidirectional"))
      (node (ref "K_?") (pin "P$2") (pinfunction "P$2_P$2") (pintype "bidirectional"))
      (node (ref "K_A") (pin "P$2") (pinfunction "P$2_P$2") (pintype "bidirectional"))
      (node (ref "K_E") (pin "P$2") (pinfunction "P$2_P$2") (pintype "bidirectional"))
      (node (ref "K_LEFT") (pin "P$2") (pinfunction "P$2_P$2") (pintype "bidirectional"))
      (node (ref "K_LEFTALT") (pin "P$2") (pinfunction "P$2_P$2") (pintype "bidirectional"))
      (node (ref "K_P") (pin "P$2") (pinfunction "P$2_P$2") (pintype "bidirectional"))
      (node (ref "K_SEMI") (pin "P$2") (pinfunction "P$2_P$2") (pintype "bidirectional"))
      (node (ref "K_USCORE") (pin "P$2") (pinfunction "P$2_P$2") (pintype "bidirectional"))
      (node (ref "K_X") (pin "P$2") (pinfunction "P$2_P$2") (pintype "bidirectional"))
    )
    (net (code "5") (name "/KEYCOLUM4") (class "Default")
      (node (ref "K_4") (pin "P$2") (pinfunction "P$2_P$2") (pintype "bidirectional"))
      (node (ref "K_C") (pin "P$2") (pinfunction "P$2_P$2") (pintype "bidirectional"))
      (node (ref "K_DOWN") (pin "P$2") (pinfunction "P$2_P$2") (pintype "bidirectional"))
      (node (ref "K_PLUS") (pin "P$2") (pinfunction "P$2_P$2") (pintype "bidirectional"))
      (node (ref "K_QUOTE") (pin "P$2") (pinfunction "P$2_P$2") (pintype "bidirectional"))
      (node (ref "K_R") (pin "P$2") (pinfunction "P$2_P$2") (pintype "bidirectional"))
      (node (ref "K_RSHIFT") (pin "P$2") (pinfunction "P$2_P$2") (pintype "bidirectional"))
      (node (ref "K_S") (pin "P$2") (pinfunction "P$2_P$2") (pintype "bidirectional"))
      (node (ref "K_SPACE") (pin "P$2") (pinfunction "P$2_P$2") (pintype "bidirectional"))
      (node (ref "K_{") (pin "P$2") (pinfunction "P$2_P$2") (pintype "bidirectional"))
    )
    (net (code "6") (name "/KEYCOLUM5") (class "Default")
      (node (ref "K-5") (pin "P$2") (pinfunction "P$2_P$2") (pintype "bidirectional"))
      (node (ref "K_D") (pin "P$2") (pinfunction "P$2_P$2") (pintype "bidirectional"))
      (node (ref "K_N") (pin "P$2") (pinfunction "P$2_P$2") (pintype "bidirectional"))
      (node (ref "K_PIPE") (pin "P$2") (pinfunction "P$2_P$2") (pintype "bidirectional"))
      (node (ref "K_RETURN") (pin "P$2") (pinfunction "P$2_P$2") (pintype "bidirectional"))
      (node (ref "K_T") (pin "P$2") (pinfunction "P$2_P$2") (pintype "bidirectional"))
      (node (ref "K_TILDE") (pin "P$2") (pinfunction "P$2_P$2") (pintype "bidirectional"))
      (node (ref "K_UP") (pin "P$2") (pinfunction "P$2_P$2") (pintype "bidirectional"))
      (node (ref "K_V") (pin "P$2") (pinfunction "P$2_P$2") (pintype "bidirectional"))
      (node (ref "K_}") (pin "P$2") (pinfunction "P$2_P$2") (pintype "bidirectional"))
    )
    (net (code "7") (name "/KEYCOLUM6") (class "Default")
      (node (ref "K_6") (pin "P$2") (pinfunction "P$2_P$2") (pintype "bidirectional"))
      (node (ref "K_B") (pin "P$2") (pinfunction "P$2_P$2") (pintype "bidirectional"))
      (node (ref "K_BACK") (pin "P$2") (pinfunction "P$2_P$2") (pintype "bidirectional"))
      (node (ref "K_BREAK") (pin "P$2") (pinfunction "P$2_P$2") (pintype "bidirectional"))
      (node (ref "K_DEL") (pin "P$2") (pinfunction "P$2_P$2") (pintype "bidirectional"))
      (node (ref "K_F") (pin "P$2") (pinfunction "P$2_P$2") (pintype "bidirectional"))
      (node (ref "K_LINE") (pin "P$2") (pinfunction "P$2_P$2") (pintype "bidirectional"))
      (node (ref "K_M") (pin "P$2") (pinfunction "P$2_P$2") (pintype "bidirectional"))
      (node (ref "K_RIGHT") (pin "P$2") (pinfunction "P$2_P$2") (pintype "bidirectional"))
      (node (ref "K_Y") (pin "P$2") (pinfunction "P$2_P$2") (pintype "bidirectional"))
    )
    (net (code "9") (name "/KEYROW0") (class "Default")
      (node (ref "K-1") (pin "P$1") (pinfunction "P$1_P$1") (pintype "bidirectional"))
      (node (ref "K-2") (pin "P$1") (pinfunction "P$1_P$1") (pintype "bidirectional"))
      (node (ref "K-5") (pin "P$1") (pinfunction "P$1_P$1") (pintype "bidirectional"))
      (node (ref "K_3") (pin "P$1") (pinfunction "P$1_P$1") (pintype "bidirectional"))
      (node (ref "K_4") (pin "P$1") (pinfunction "P$1_P$1") (pintype "bidirectional"))
      (node (ref "K_6") (pin "P$1") (pinfunction "P$1_P$1") (pintype "bidirectional"))
      (node (ref "K_ESC") (pin "P$1") (pinfunction "P$1_P$1") (pintype "bidirectional"))
    )
    (net (code "10") (name "/KEYROW1") (class "Default")
      (node (ref "K_E") (pin "P$1") (pinfunction "P$1_P$1") (pintype "bidirectional"))
      (node (ref "K_Q") (pin "P$1") (pinfunction "P$1_P$1") (pintype "bidirectional"))
      (node (ref "K_R") (pin "P$1") (pinfunction "P$1_P$1") (pintype "bidirectional"))
      (node (ref "K_SETUP") (pin "P$1") (pinfunction "P$1_P$1") (pintype "bidirectional"))
      (node (ref "K_T") (pin "P$1") (pinfunction "P$1_P$1") (pintype "bidirectional"))
      (node (ref "K_W") (pin "P$1") (pinfunction "P$1_P$1") (pintype "bidirectional"))
      (node (ref "K_Y") (pin "P$1") (pinfunction "P$1_P$1") (pintype "bidirectional"))
    )
    (net (code "11") (name "/KEYROW2") (class "Default")
      (node (ref "K_A") (pin "P$1") (pinfunction "P$1_P$1") (pintype "bidirectional"))
      (node (ref "K_CAPS") (pin "P$1") (pinfunction "P$1_P$1") (pintype "bidirectional"))
      (node (ref "K_CONTROL") (pin "P$1") (pinfunction "P$1_P$1") (pintype "bidirectional"))
      (node (ref "K_D") (pin "P$1") (pinfunction "P$1_P$1") (pintype "bidirectional"))
      (node (ref "K_F") (pin "P$1") (pinfunction "P$1_P$1") (pintype "bidirectional"))
      (node (ref "K_S") (pin "P$1") (pinfunction "P$1_P$1") (pintype "bidirectional"))
      (node (ref "K_TAB") (pin "P$1") (pinfunction "P$1_P$1") (pintype "bidirectional"))
    )
    (net (code "12") (name "/KEYROW3") (class "Default")
      (node (ref "K_B") (pin "P$1") (pinfunction "P$1_P$1") (pintype "bidirectional"))
      (node (ref "K_C") (pin "P$1") (pinfunction "P$1_P$1") (pintype "bidirectional"))
      (node (ref "K_LSHIFT") (pin "P$1") (pinfunction "P$1_P$1") (pintype "bidirectional"))
      (node (ref "K_NOSCL") (pin "P$1") (pinfunction "P$1_P$1") (pintype "bidirectional"))
      (node (ref "K_V") (pin "P$1") (pinfunction "P$1_P$1") (pintype "bidirectional"))
      (node (ref "K_X") (pin "P$1") (pinfunction "P$1_P$1") (pintype "bidirectional"))
      (node (ref "K_Z") (pin "P$1") (pinfunction "P$1_P$1") (pintype "bidirectional"))
    )
    (net (code "13") (name "/KEYROW4") (class "Default")
      (node (ref "K_LEFTALT") (pin "P$1") (pinfunction "P$1_P$1") (pintype "bidirectional"))
      (node (ref "K_LEFTMETA") (pin "P$1") (pinfunction "P$1_P$1") (pintype "bidirectional"))
      (node (ref "K_M") (pin "P$1") (pinfunction "P$1_P$1") (pintype "bidirectional"))
      (node (ref "K_N") (pin "P$1") (pinfunction "P$1_P$1") (pintype "bidirectional"))
      (node (ref "K_RIGHTALT") (pin "P$1") (pinfunction "P$1_P$1") (pintype "bidirectional"))
      (node (ref "K_RIGHTMETA") (pin "P$1") (pinfunction "P$1_P$1") (pintype "bidirectional"))
      (node (ref "K_SPACE") (pin "P$1") (pinfunction "P$1_P$1") (pintype "bidirectional"))
    )
    (net (code "14") (name "/KEYROW5") (class "Default")
      (node (ref "K_7") (pin "P$1") (pinfunction "P$1_P$1") (pintype "bidirectional"))
      (node (ref "K_8") (pin "P$1") (pinfunction "P$1_P$1") (pintype "bidirectional"))
      (node (ref "K_9") (pin "P$1") (pinfunction "P$1_P$1") (pintype "bidirectional"))
      (node (ref "K_DOWN") (pin "P$1") (pinfunction "P$1_P$1") (pintype "bidirectional"))
      (node (ref "K_LEFT") (pin "P$1") (pinfunction "P$1_P$1") (pintype "bidirectional"))
      (node (ref "K_RIGHT") (pin "P$1") (pinfunction "P$1_P$1") (pintype "bidirectional"))
      (node (ref "K_UP") (pin "P$1") (pinfunction "P$1_P$1") (pintype "bidirectional"))
    )
    (net (code "15") (name "/KEYROW6") (class "Default")
      (node (ref "K_0") (pin "P$1") (pinfunction "P$1_P$1") (pintype "bidirectional"))
      (node (ref "K_BACK") (pin "P$1") (pinfunction "P$1_P$1") (pintype "bidirectional"))
      (node (ref "K_I") (pin "P$1") (pinfunction "P$1_P$1") (pintype "bidirectional"))
      (node (ref "K_PLUS") (pin "P$1") (pinfunction "P$1_P$1") (pintype "bidirectional"))
      (node (ref "K_TILDE") (pin "P$1") (pinfunction "P$1_P$1") (pintype "bidirectional"))
      (node (ref "K_U") (pin "P$1") (pinfunction "P$1_P$1") (pintype "bidirectional"))
      (node (ref "K_USCORE") (pin "P$1") (pinfunction "P$1_P$1") (pintype "bidirectional"))
    )
    (net (code "16") (name "/KEYROW7") (class "Default")
      (node (ref "K_BREAK") (pin "P$1") (pinfunction "P$1_P$1") (pintype "bidirectional"))
      (node (ref "K_G") (pin "P$1") (pinfunction "P$1_P$1") (pintype "bidirectional"))
      (node (ref "K_H") (pin "P$1") (pinfunction "P$1_P$1") (pintype "bidirectional"))
      (node (ref "K_O") (pin "P$1") (pinfunction "P$1_P$1") (pintype "bidirectional"))
      (node (ref "K_P") (pin "P$1") (pinfunction "P$1_P$1") (pintype "bidirectional"))
      (node (ref "K_{") (pin "P$1") (pinfunction "P$1_P$1") (pintype "bidirectional"))
      (node (ref "K_}") (pin "P$1") (pinfunction "P$1_P$1") (pintype "bidirectional"))
    )
    (net (code "17") (name "/KEYROW8") (class "Default")
      (node (ref "K_DEL") (pin "P$1") (pinfunction "P$1_P$1") (pintype "bidirectional"))
      (node (ref "K_J") (pin "P$1") (pinfunction "P$1_P$1") (pintype "bidirectional"))
      (node (ref "K_K") (pin "P$1") (pinfunction "P$1_P$1") (pintype "bidirectional"))
      (node (ref "K_L") (pin "P$1") (pinfunction "P$1_P$1") (pintype "bidirectional"))
      (node (ref "K_QUOTE") (pin "P$1") (pinfunction "P$1_P$1") (pintype "bidirectional"))
      (node (ref "K_RETURN") (pin "P$1") (pinfunction "P$1_P$1") (pintype "bidirectional"))
      (node (ref "K_SEMI") (pin "P$1") (pinfunction "P$1_P$1") (pintype "bidirectional"))
    )
    (net (code "18") (name "/KEYROW9") (class "Default")
      (node (ref "K_<") (pin "P$1") (pinfunction "P$1_P$1") (pintype "bidirectional"))
      (node (ref "K_>") (pin "P$1") (pinfunction "P$1_P$1") (pintype "bidirectional"))
      (node (ref "K_?") (pin "P$1") (pinfunction "P$1_P$1") (pintype "bidirectional"))
      (node (ref "K_LINE") (pin "P$1") (pinfunction "P$1_P$1") (pintype "bidirectional"))
      (node (ref "K_PIPE") (pin "P$1") (pinfunction "P$1_P$1") (pintype "bidirectional"))
      (node (ref "K_RSHIFT") (pin "P$1") (pinfunction "P$1_P$1") (pintype "bidirectional"))
    )
    (net (code "20") (name "unconnected-(0-P0-PadMX1)") (class "Default")
      (node (ref "0") (pin "MX1") (pinfunction "P0_MX1") (pintype "bidirectional"))
    )
    (net (code "21") (name "unconnected-(0-P1-PadMX2)") (class "Default")
      (node (ref "0") (pin "MX2") (pinfunction "P1_MX2") (pintype "bidirectional"))
    )
    (net (code "22") (name "unconnected-(1-P0-PadMX1)") (class "Default")
      (node (ref "1") (pin "MX1") (pinfunction "P0_MX1") (pintype "bidirectional"))
    )
    (net (code "23") (name "unconnected-(1-P1-PadMX2)") (class "Default")
      (node (ref "1") (pin "MX2") (pinfunction "P1_MX2") (pintype "bidirectional"))
    )
    (net (code "24") (name "unconnected-(2-P0-PadMX1)") (class "Default")
      (node (ref "2") (pin "MX1") (pinfunction "P0_MX1") (pintype "bidirectional"))
    )
    (net (code "25") (name "unconnected-(2-P1-PadMX2)") (class "Default")
      (node (ref "2") (pin "MX2") (pinfunction "P1_MX2") (pintype "bidirectional"))
    )
    (net (code "26") (name "unconnected-(3-P0-PadMX1)") (class "Default")
      (node (ref "3") (pin "MX1") (pinfunction "P0_MX1") (pintype "bidirectional"))
    )
    (net (code "27") (name "unconnected-(3-P1-PadMX2)") (class "Default")
      (node (ref "3") (pin "MX2") (pinfunction "P1_MX2") (pintype "bidirectional"))
    )
    (net (code "28") (name "unconnected-(4-P0-PadMX1)") (class "Default")
      (node (ref "4") (pin "MX1") (pinfunction "P0_MX1") (pintype "bidirectional"))
    )
    (net (code "29") (name "unconnected-(4-P1-PadMX2)") (class "Default")
      (node (ref "4") (pin "MX2") (pinfunction "P1_MX2") (pintype "bidirectional"))
    )
    (net (code "30") (name "unconnected-(5-P0-PadMX1)") (class "Default")
      (node (ref "5") (pin "MX1") (pinfunction "P0_MX1") (pintype "bidirectional"))
    )
    (net (code "31") (name "unconnected-(5-P1-PadMX2)") (class "Default")
      (node (ref "5") (pin "MX2") (pinfunction "P1_MX2") (pintype "bidirectional"))
    )
    (net (code "32") (name "unconnected-(6-P0-PadMX1)") (class "Default")
      (node (ref "6") (pin "MX1") (pinfunction "P0_MX1") (pintype "bidirectional"))
    )
    (net (code "33") (name "unconnected-(6-P1-PadMX2)") (class "Default")
      (node (ref "6") (pin "MX2") (pinfunction "P1_MX2") (pintype "bidirectional"))
    )
    (net (code "34") (name "unconnected-(7-P0-PadMX1)") (class "Default")
      (node (ref "7") (pin "MX1") (pinfunction "P0_MX1") (pintype "bidirectional"))
    )
    (net (code "35") (name "unconnected-(7-P1-PadMX2)") (class "Default")
      (node (ref "7") (pin "MX2") (pinfunction "P1_MX2") (pintype "bidirectional"))
    )
    (net (code "36") (name "unconnected-(8-P0-PadMX1)") (class "Default")
      (node (ref "8") (pin "MX1") (pinfunction "P0_MX1") (pintype "bidirectional"))
    )
    (net (code "37") (name "unconnected-(8-P1-PadMX2)") (class "Default")
      (node (ref "8") (pin "MX2") (pinfunction "P1_MX2") (pintype "bidirectional"))
    )
    (net (code "38") (name "unconnected-(9-P0-PadMX1)") (class "Default")
      (node (ref "9") (pin "MX1") (pinfunction "P0_MX1") (pintype "bidirectional"))
    )
    (net (code "39") (name "unconnected-(9-P1-PadMX2)") (class "Default")
      (node (ref "9") (pin "MX2") (pinfunction "P1_MX2") (pintype "bidirectional"))
    )
    (net (code "40") (name "unconnected-(A-P0-PadMX1)") (class "Default")
      (node (ref "A") (pin "MX1") (pinfunction "P0_MX1") (pintype "bidirectional"))
    )
    (net (code "41") (name "unconnected-(A-P1-PadMX2)") (class "Default")
      (node (ref "A") (pin "MX2") (pinfunction "P1_MX2") (pintype "bidirectional"))
    )
    (net (code "42") (name "unconnected-(ALT-P0-PadMX1)") (class "Default")
      (node (ref "ALT") (pin "MX1") (pinfunction "P0_MX1") (pintype "bidirectional"))
    )
    (net (code "43") (name "unconnected-(ALT-P1-PadMX2)") (class "Default")
      (node (ref "ALT") (pin "MX2") (pinfunction "P1_MX2") (pintype "bidirectional"))
    )
    (net (code "44") (name "unconnected-(ALT2-P0-PadMX1)") (class "Default")
      (node (ref "ALT2") (pin "MX1") (pinfunction "P0_MX1") (pintype "bidirectional"))
    )
    (net (code "45") (name "unconnected-(ALT2-P1-PadMX2)") (class "Default")
      (node (ref "ALT2") (pin "MX2") (pinfunction "P1_MX2") (pintype "bidirectional"))
    )
    (net (code "46") (name "unconnected-(B-P0-PadMX1)") (class "Default")
      (node (ref "B") (pin "MX1") (pinfunction "P0_MX1") (pintype "bidirectional"))
    )
    (net (code "47") (name "unconnected-(B-P1-PadMX2)") (class "Default")
      (node (ref "B") (pin "MX2") (pinfunction "P1_MX2") (pintype "bidirectional"))
    )
    (net (code "48") (name "unconnected-(BACK-P0-PadMX1)") (class "Default")
      (node (ref "BACK") (pin "MX1") (pinfunction "P0_MX1") (pintype "bidirectional"))
    )
    (net (code "49") (name "unconnected-(BACK-P1-PadMX2)") (class "Default")
      (node (ref "BACK") (pin "MX2") (pinfunction "P1_MX2") (pintype "bidirectional"))
    )
    (net (code "50") (name "unconnected-(BRK-P0-PadMX1)") (class "Default")
      (node (ref "BRK") (pin "MX1") (pinfunction "P0_MX1") (pintype "bidirectional"))
    )
    (net (code "51") (name "unconnected-(BRK-P1-PadMX2)") (class "Default")
      (node (ref "BRK") (pin "MX2") (pinfunction "P1_MX2") (pintype "bidirectional"))
    )
    (net (code "52") (name "unconnected-(C-P0-PadMX1)") (class "Default")
      (node (ref "C") (pin "MX1") (pinfunction "P0_MX1") (pintype "bidirectional"))
    )
    (net (code "53") (name "unconnected-(C-P1-PadMX2)") (class "Default")
      (node (ref "C") (pin "MX2") (pinfunction "P1_MX2") (pintype "bidirectional"))
    )
    (net (code "54") (name "unconnected-(CAPS-P0-PadMX1)") (class "Default")
      (node (ref "CAPS") (pin "MX1") (pinfunction "P0_MX1") (pintype "bidirectional"))
    )
    (net (code "55") (name "unconnected-(CAPS-P1-PadMX2)") (class "Default")
      (node (ref "CAPS") (pin "MX2") (pinfunction "P1_MX2") (pintype "bidirectional"))
    )
    (net (code "56") (name "unconnected-(COMMA-P0-PadMX1)") (class "Default")
      (node (ref "COMMA") (pin "MX1") (pinfunction "P0_MX1") (pintype "bidirectional"))
    )
    (net (code "57") (name "unconnected-(COMMA-P1-PadMX2)") (class "Default")
      (node (ref "COMMA") (pin "MX2") (pinfunction "P1_MX2") (pintype "bidirectional"))
    )
    (net (code "58") (name "unconnected-(CTRL-P0-PadMX1)") (class "Default")
      (node (ref "CTRL") (pin "MX1") (pinfunction "P0_MX1") (pintype "bidirectional"))
    )
    (net (code "59") (name "unconnected-(CTRL-P1-PadMX2)") (class "Default")
      (node (ref "CTRL") (pin "MX2") (pinfunction "P1_MX2") (pintype "bidirectional"))
    )
    (net (code "60") (name "unconnected-(D-P0-PadMX1)") (class "Default")
      (node (ref "D") (pin "MX1") (pinfunction "P0_MX1") (pintype "bidirectional"))
    )
    (net (code "61") (name "unconnected-(D-P1-PadMX2)") (class "Default")
      (node (ref "D") (pin "MX2") (pinfunction "P1_MX2") (pintype "bidirectional"))
    )
    (net (code "62") (name "unconnected-(DEL-P0-PadMX1)") (class "Default")
      (node (ref "DEL") (pin "MX1") (pinfunction "P0_MX1") (pintype "bidirectional"))
    )
    (net (code "63") (name "unconnected-(DEL-P1-PadMX2)") (class "Default")
      (node (ref "DEL") (pin "MX2") (pinfunction "P1_MX2") (pintype "bidirectional"))
    )
    (net (code "64") (name "unconnected-(DOWN-P0-PadMX1)") (class "Default")
      (node (ref "DOWN") (pin "MX1") (pinfunction "P0_MX1") (pintype "bidirectional"))
    )
    (net (code "65") (name "unconnected-(DOWN-P1-PadMX2)") (class "Default")
      (node (ref "DOWN") (pin "MX2") (pinfunction "P1_MX2") (pintype "bidirectional"))
    )
    (net (code "66") (name "unconnected-(E-P0-PadMX1)") (class "Default")
      (node (ref "E") (pin "MX1") (pinfunction "P0_MX1") (pintype "bidirectional"))
    )
    (net (code "67") (name "unconnected-(E-P1-PadMX2)") (class "Default")
      (node (ref "E") (pin "MX2") (pinfunction "P1_MX2") (pintype "bidirectional"))
    )
    (net (code "68") (name "unconnected-(EQUAL-P0-PadMX1)") (class "Default")
      (node (ref "EQUAL") (pin "MX1") (pinfunction "P0_MX1") (pintype "bidirectional"))
    )
    (net (code "69") (name "unconnected-(EQUAL-P1-PadMX2)") (class "Default")
      (node (ref "EQUAL") (pin "MX2") (pinfunction "P1_MX2") (pintype "bidirectional"))
    )
    (net (code "70") (name "unconnected-(ESC-P0-PadMX1)") (class "Default")
      (node (ref "ESC") (pin "MX1") (pinfunction "P0_MX1") (pintype "bidirectional"))
    )
    (net (code "71") (name "unconnected-(ESC-P1-PadMX2)") (class "Default")
      (node (ref "ESC") (pin "MX2") (pinfunction "P1_MX2") (pintype "bidirectional"))
    )
    (net (code "72") (name "unconnected-(F-P0-PadMX1)") (class "Default")
      (node (ref "F") (pin "MX1") (pinfunction "P0_MX1") (pintype "bidirectional"))
    )
    (net (code "73") (name "unconnected-(F-P1-PadMX2)") (class "Default")
      (node (ref "F") (pin "MX2") (pinfunction "P1_MX2") (pintype "bidirectional"))
    )
    (net (code "74") (name "unconnected-(G-P0-PadMX1)") (class "Default")
      (node (ref "G") (pin "MX1") (pinfunction "P0_MX1") (pintype "bidirectional"))
    )
    (net (code "75") (name "unconnected-(G-P1-PadMX2)") (class "Default")
      (node (ref "G") (pin "MX2") (pinfunction "P1_MX2") (pintype "bidirectional"))
    )
    (net (code "76") (name "unconnected-(GRAVE-P0-PadMX1)") (class "Default")
      (node (ref "GRAVE") (pin "MX1") (pinfunction "P0_MX1") (pintype "bidirectional"))
    )
    (net (code "77") (name "unconnected-(GRAVE-P1-PadMX2)") (class "Default")
      (node (ref "GRAVE") (pin "MX2") (pinfunction "P1_MX2") (pintype "bidirectional"))
    )
    (net (code "78") (name "unconnected-(H-P0-PadMX1)") (class "Default")
      (node (ref "H") (pin "MX1") (pinfunction "P0_MX1") (pintype "bidirectional"))
    )
    (net (code "79") (name "unconnected-(H-P1-PadMX2)") (class "Default")
      (node (ref "H") (pin "MX2") (pinfunction "P1_MX2") (pintype "bidirectional"))
    )
    (net (code "80") (name "unconnected-(I-P0-PadMX1)") (class "Default")
      (node (ref "I") (pin "MX1") (pinfunction "P0_MX1") (pintype "bidirectional"))
    )
    (net (code "81") (name "unconnected-(I-P1-PadMX2)") (class "Default")
      (node (ref "I") (pin "MX2") (pinfunction "P1_MX2") (pintype "bidirectional"))
    )
    (net (code "82") (name "unconnected-(J-P0-PadMX1)") (class "Default")
      (node (ref "J") (pin "MX1") (pinfunction "P0_MX1") (pintype "bidirectional"))
    )
    (net (code "83") (name "unconnected-(J-P1-PadMX2)") (class "Default")
      (node (ref "J") (pin "MX2") (pinfunction "P1_MX2") (pintype "bidirectional"))
    )
    (net (code "84") (name "unconnected-(K-P0-PadMX1)") (class "Default")
      (node (ref "K") (pin "MX1") (pinfunction "P0_MX1") (pintype "bidirectional"))
    )
    (net (code "85") (name "unconnected-(K-P1-PadMX2)") (class "Default")
      (node (ref "K") (pin "MX2") (pinfunction "P1_MX2") (pintype "bidirectional"))
    )
    (net (code "86") (name "unconnected-(KP_DASH-P0-PadMX1)") (class "Default")
      (node (ref "KP_DASH") (pin "MX1") (pinfunction "P0_MX1") (pintype "bidirectional"))
    )
    (net (code "87") (name "unconnected-(KP_DASH-P1-PadMX2)") (class "Default")
      (node (ref "KP_DASH") (pin "MX2") (pinfunction "P1_MX2") (pintype "bidirectional"))
    )
    (net (code "88") (name "unconnected-(L-P0-PadMX1)") (class "Default")
      (node (ref "L") (pin "MX1") (pinfunction "P0_MX1") (pintype "bidirectional"))
    )
    (net (code "89") (name "unconnected-(L-P1-PadMX2)") (class "Default")
      (node (ref "L") (pin "MX2") (pinfunction "P1_MX2") (pintype "bidirectional"))
    )
    (net (code "90") (name "unconnected-(LBRACKET-P0-PadMX1)") (class "Default")
      (node (ref "LBRACKET") (pin "MX1") (pinfunction "P0_MX1") (pintype "bidirectional"))
    )
    (net (code "91") (name "unconnected-(LBRACKET-P1-PadMX2)") (class "Default")
      (node (ref "LBRACKET") (pin "MX2") (pinfunction "P1_MX2") (pintype "bidirectional"))
    )
    (net (code "92") (name "unconnected-(LEFT-P0-PadMX1)") (class "Default")
      (node (ref "LEFT") (pin "MX1") (pinfunction "P0_MX1") (pintype "bidirectional"))
    )
    (net (code "93") (name "unconnected-(LEFT-P1-PadMX2)") (class "Default")
      (node (ref "LEFT") (pin "MX2") (pinfunction "P1_MX2") (pintype "bidirectional"))
    )
    (net (code "94") (name "unconnected-(LINE-P0-PadMX1)") (class "Default")
      (node (ref "LINE") (pin "MX1") (pinfunction "P0_MX1") (pintype "bidirectional"))
    )
    (net (code "95") (name "unconnected-(LINE-P1-PadMX2)") (class "Default")
      (node (ref "LINE") (pin "MX2") (pinfunction "P1_MX2") (pintype "bidirectional"))
    )
    (net (code "96") (name "unconnected-(M-P0-PadMX1)") (class "Default")
      (node (ref "M") (pin "MX1") (pinfunction "P0_MX1") (pintype "bidirectional"))
    )
    (net (code "97") (name "unconnected-(M-P1-PadMX2)") (class "Default")
      (node (ref "M") (pin "MX2") (pinfunction "P1_MX2") (pintype "bidirectional"))
    )
    (net (code "98") (name "unconnected-(META-P0-PadMX1)") (class "Default")
      (node (ref "META") (pin "MX1") (pinfunction "P0_MX1") (pintype "bidirectional"))
    )
    (net (code "99") (name "unconnected-(META-P1-PadMX2)") (class "Default")
      (node (ref "META") (pin "MX2") (pinfunction "P1_MX2") (pintype "bidirectional"))
    )
    (net (code "100") (name "unconnected-(META2-P0-PadMX1)") (class "Default")
      (node (ref "META2") (pin "MX1") (pinfunction "P0_MX1") (pintype "bidirectional"))
    )
    (net (code "101") (name "unconnected-(META2-P1-PadMX2)") (class "Default")
      (node (ref "META2") (pin "MX2") (pinfunction "P1_MX2") (pintype "bidirectional"))
    )
    (net (code "102") (name "unconnected-(N-P0-PadMX1)") (class "Default")
      (node (ref "N") (pin "MX1") (pinfunction "P0_MX1") (pintype "bidirectional"))
    )
    (net (code "103") (name "unconnected-(N-P1-PadMX2)") (class "Default")
      (node (ref "N") (pin "MX2") (pinfunction "P1_MX2") (pintype "bidirectional"))
    )
    (net (code "104") (name "unconnected-(NO-P0-PadMX1)") (class "Default")
      (node (ref "NO") (pin "MX1") (pinfunction "P0_MX1") (pintype "bidirectional"))
    )
    (net (code "105") (name "unconnected-(NO-P1-PadMX2)") (class "Default")
      (node (ref "NO") (pin "MX2") (pinfunction "P1_MX2") (pintype "bidirectional"))
    )
    (net (code "106") (name "unconnected-(O-P0-PadMX1)") (class "Default")
      (node (ref "O") (pin "MX1") (pinfunction "P0_MX1") (pintype "bidirectional"))
    )
    (net (code "107") (name "unconnected-(O-P1-PadMX2)") (class "Default")
      (node (ref "O") (pin "MX2") (pinfunction "P1_MX2") (pintype "bidirectional"))
    )
    (net (code "108") (name "unconnected-(P-P0-PadMX1)") (class "Default")
      (node (ref "P") (pin "MX1") (pinfunction "P0_MX1") (pintype "bidirectional"))
    )
    (net (code "109") (name "unconnected-(P-P1-PadMX2)") (class "Default")
      (node (ref "P") (pin "MX2") (pinfunction "P1_MX2") (pintype "bidirectional"))
    )
    (net (code "110") (name "unconnected-(PERIOD-P0-PadMX1)") (class "Default")
      (node (ref "PERIOD") (pin "MX1") (pinfunction "P0_MX1") (pintype "bidirectional"))
    )
    (net (code "111") (name "unconnected-(PERIOD-P1-PadMX2)") (class "Default")
      (node (ref "PERIOD") (pin "MX2") (pinfunction "P1_MX2") (pintype "bidirectional"))
    )
    (net (code "112") (name "unconnected-(Q-P0-PadMX1)") (class "Default")
      (node (ref "Q") (pin "MX1") (pinfunction "P0_MX1") (pintype "bidirectional"))
    )
    (net (code "113") (name "unconnected-(Q-P1-PadMX2)") (class "Default")
      (node (ref "Q") (pin "MX2") (pinfunction "P1_MX2") (pintype "bidirectional"))
    )
    (net (code "114") (name "unconnected-(QUOTE-P0-PadMX1)") (class "Default")
      (node (ref "QUOTE") (pin "MX1") (pinfunction "P0_MX1") (pintype "bidirectional"))
    )
    (net (code "115") (name "unconnected-(QUOTE-P1-PadMX2)") (class "Default")
      (node (ref "QUOTE") (pin "MX2") (pinfunction "P1_MX2") (pintype "bidirectional"))
    )
    (net (code "116") (name "unconnected-(R-P0-PadMX1)") (class "Default")
      (node (ref "R") (pin "MX1") (pinfunction "P0_MX1") (pintype "bidirectional"))
    )
    (net (code "117") (name "unconnected-(R-P1-PadMX2)") (class "Default")
      (node (ref "R") (pin "MX2") (pinfunction "P1_MX2") (pintype "bidirectional"))
    )
    (net (code "118") (name "unconnected-(RBRACKET-P0-PadMX1)") (class "Default")
      (node (ref "RBRACKET") (pin "MX1") (pinfunction "P0_MX1") (pintype "bidirectional"))
    )
    (net (code "119") (name "unconnected-(RBRACKET-P1-PadMX2)") (class "Default")
      (node (ref "RBRACKET") (pin "MX2") (pinfunction "P1_MX2") (pintype "bidirectional"))
    )
    (net (code "120") (name "unconnected-(RIGHT-P0-PadMX1)") (class "Default")
      (node (ref "RIGHT") (pin "MX1") (pinfunction "P0_MX1") (pintype "bidirectional"))
    )
    (net (code "121") (name "unconnected-(RIGHT-P1-PadMX2)") (class "Default")
      (node (ref "RIGHT") (pin "MX2") (pinfunction "P1_MX2") (pintype "bidirectional"))
    )
    (net (code "122") (name "unconnected-(S-P0-PadMX1)") (class "Default")
      (node (ref "S") (pin "MX1") (pinfunction "P0_MX1") (pintype "bidirectional"))
    )
    (net (code "123") (name "unconnected-(S-P1-PadMX2)") (class "Default")
      (node (ref "S") (pin "MX2") (pinfunction "P1_MX2") (pintype "bidirectional"))
    )
    (net (code "124") (name "unconnected-(SEMI-P0-PadMX1)") (class "Default")
      (node (ref "SEMI") (pin "MX1") (pinfunction "P0_MX1") (pintype "bidirectional"))
    )
    (net (code "125") (name "unconnected-(SEMI-P1-PadMX2)") (class "Default")
      (node (ref "SEMI") (pin "MX2") (pinfunction "P1_MX2") (pintype "bidirectional"))
    )
    (net (code "126") (name "unconnected-(SHIFT-P0-PadMX1)") (class "Default")
      (node (ref "SHIFT") (pin "MX1") (pinfunction "P0_MX1") (pintype "bidirectional"))
    )
    (net (code "127") (name "unconnected-(SHIFT-P1-PadMX2)") (class "Default")
      (node (ref "SHIFT") (pin "MX2") (pinfunction "P1_MX2") (pintype "bidirectional"))
    )
    (net (code "128") (name "unconnected-(SHIFT2-P0-PadMX1)") (class "Default")
      (node (ref "SHIFT2") (pin "MX1") (pinfunction "P0_MX1") (pintype "bidirectional"))
    )
    (net (code "129") (name "unconnected-(SHIFT2-P1-PadMX2)") (class "Default")
      (node (ref "SHIFT2") (pin "MX2") (pinfunction "P1_MX2") (pintype "bidirectional"))
    )
    (net (code "130") (name "unconnected-(SPACE-P0-PadMX1)") (class "Default")
      (node (ref "SPACE") (pin "MX1") (pinfunction "P0_MX1") (pintype "bidirectional"))
    )
    (net (code "131") (name "unconnected-(SPACE-P1-PadMX2)") (class "Default")
      (node (ref "SPACE") (pin "MX2") (pinfunction "P1_MX2") (pintype "bidirectional"))
    )
    (net (code "132") (name "unconnected-(SPACE2-P0-PadMX1)") (class "Default")
      (node (ref "SPACE2") (pin "MX1") (pinfunction "P0_MX1") (pintype "bidirectional"))
    )
    (net (code "133") (name "unconnected-(SPACE2-P1-PadMX2)") (class "Default")
      (node (ref "SPACE2") (pin "MX2") (pinfunction "P1_MX2") (pintype "bidirectional"))
    )
    (net (code "134") (name "unconnected-(SPACE3-P0-PadMX1)") (class "Default")
      (node (ref "SPACE3") (pin "MX1") (pinfunction "P0_MX1") (pintype "bidirectional"))
    )
    (net (code "135") (name "unconnected-(SPACE3-P1-PadMX2)") (class "Default")
      (node (ref "SPACE3") (pin "MX2") (pinfunction "P1_MX2") (pintype "bidirectional"))
    )
    (net (code "136") (name "unconnected-(T-P0-PadMX1)") (class "Default")
      (node (ref "T") (pin "MX1") (pinfunction "P0_MX1") (pintype "bidirectional"))
    )
    (net (code "137") (name "unconnected-(T-P1-PadMX2)") (class "Default")
      (node (ref "T") (pin "MX2") (pinfunction "P1_MX2") (pintype "bidirectional"))
    )
    (net (code "138") (name "unconnected-(TAB-P0-PadMX1)") (class "Default")
      (node (ref "TAB") (pin "MX1") (pinfunction "P0_MX1") (pintype "bidirectional"))
    )
    (net (code "139") (name "unconnected-(TAB-P1-PadMX2)") (class "Default")
      (node (ref "TAB") (pin "MX2") (pinfunction "P1_MX2") (pintype "bidirectional"))
    )
    (net (code "140") (name "unconnected-(U-P0-PadMX1)") (class "Default")
      (node (ref "U") (pin "MX1") (pinfunction "P0_MX1") (pintype "bidirectional"))
    )
    (net (code "141") (name "unconnected-(U-P1-PadMX2)") (class "Default")
      (node (ref "U") (pin "MX2") (pinfunction "P1_MX2") (pintype "bidirectional"))
    )
    (net (code "142") (name "unconnected-(UP-P0-PadMX1)") (class "Default")
      (node (ref "UP") (pin "MX1") (pinfunction "P0_MX1") (pintype "bidirectional"))
    )
    (net (code "143") (name "unconnected-(UP-P1-PadMX2)") (class "Default")
      (node (ref "UP") (pin "MX2") (pinfunction "P1_MX2") (pintype "bidirectional"))
    )
    (net (code "144") (name "unconnected-(V-P0-PadMX1)") (class "Default")
      (node (ref "V") (pin "MX1") (pinfunction "P0_MX1") (pintype "bidirectional"))
    )
    (net (code "145") (name "unconnected-(V-P1-PadMX2)") (class "Default")
      (node (ref "V") (pin "MX2") (pinfunction "P1_MX2") (pintype "bidirectional"))
    )
    (net (code "146") (name "unconnected-(W-P0-PadMX1)") (class "Default")
      (node (ref "W") (pin "MX1") (pinfunction "P0_MX1") (pintype "bidirectional"))
    )
    (net (code "147") (name "unconnected-(W-P1-PadMX2)") (class "Default")
      (node (ref "W") (pin "MX2") (pinfunction "P1_MX2") (pintype "bidirectional"))
    )
    (net (code "148") (name "unconnected-(X-P0-PadMX1)") (class "Default")
      (node (ref "X") (pin "MX1") (pinfunction "P0_MX1") (pintype "bidirectional"))
    )
    (net (code "149") (name "unconnected-(X-P1-PadMX2)") (class "Default")
      (node (ref "X") (pin "MX2") (pinfunction "P1_MX2") (pintype "bidirectional"))
    )
    (net (code "150") (name "unconnected-(Y-P0-PadMX1)") (class "Default")
      (node (ref "Y") (pin "MX1") (pinfunction "P0_MX1") (pintype "bidirectional"))
    )
    (net (code "151") (name "unconnected-(Y-P1-PadMX2)") (class "Default")
      (node (ref "Y") (pin "MX2") (pinfunction "P1_MX2") (pintype "bidirectional"))
    )
    (net (code "152") (name "unconnected-(Z-P0-PadMX1)") (class "Default")
      (node (ref "Z") (pin "MX1") (pinfunction "P0_MX1") (pintype "bidirectional"))
    )
    (net (code "153") (name "unconnected-(Z-P1-PadMX2)") (class "Default")
      (node (ref "Z") (pin "MX2") (pinfunction "P1_MX2") (pintype "bidirectional"))
    )
    (net (code "154") (name "unconnected-(\\|-P0-PadMX1)") (class "Default")
      (node (ref "\\|") (pin "MX1") (pinfunction "P0_MX1") (pintype "bidirectional"))
    )
    (net (code "155") (name "unconnected-(\\|-P1-PadMX2)") (class "Default")
      (node (ref "\\|") (pin "MX2") (pinfunction "P1_MX2") (pintype "bidirectional"))
    )
  )
)
